# zero_board.net
KiCad netlist of a schematic drawn in EAGLE
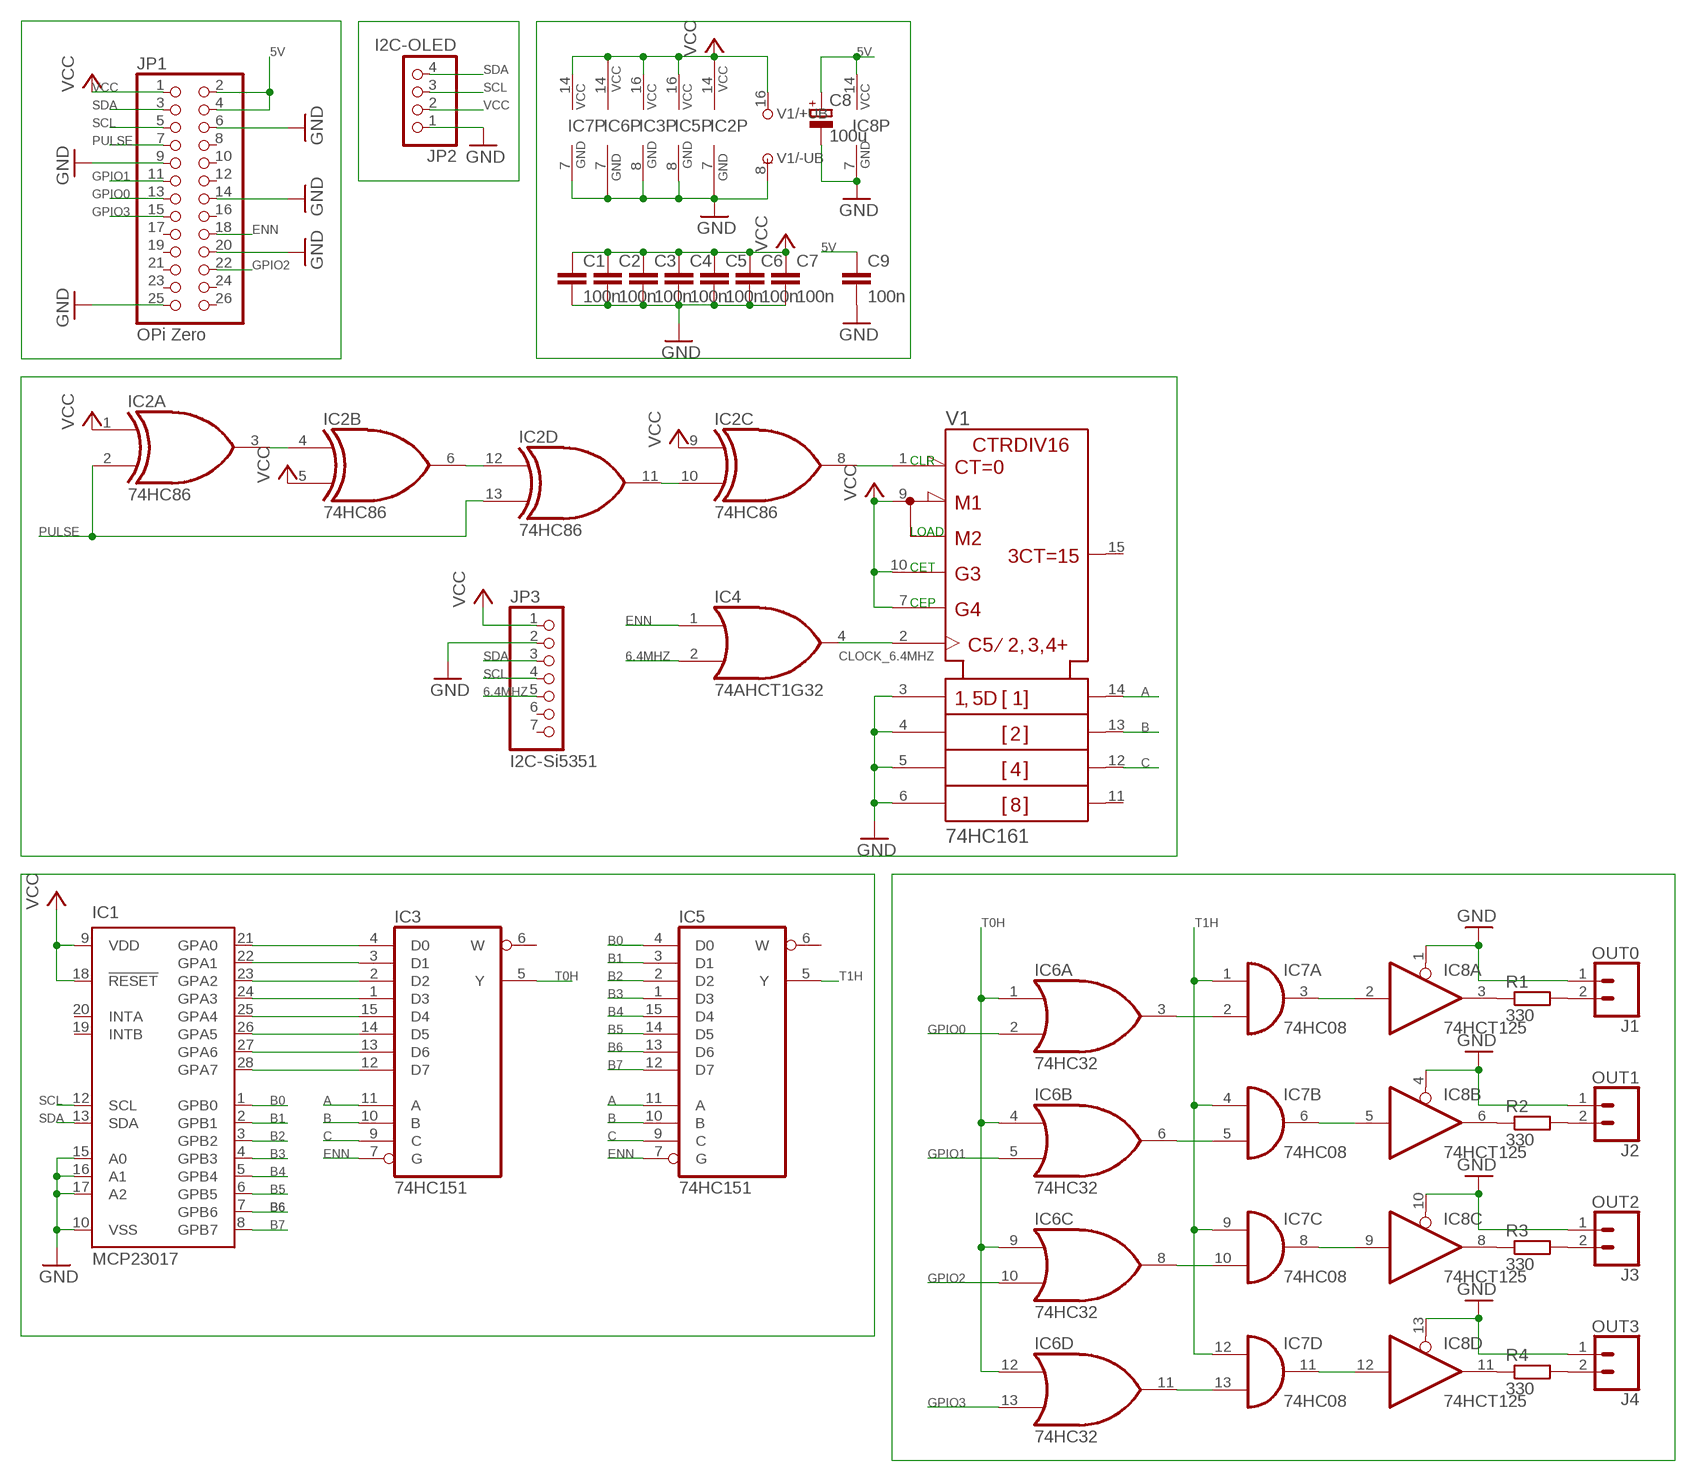
[diagram p0: schematic, sheet 1]

(export (version "E")
  (design (tool "Eeschema 10.0.6"))
  (components
    (comp (ref "C1")
      (value "100n")
      (footprint "eagle-import:C050-024X044")
      (libsource (lib "eagle-import") (part "C-EU050-024X044"))
    )
    (comp (ref "C2")
      (value "100n")
      (footprint "eagle-import:C050-024X044")
      (libsource (lib "eagle-import") (part "C-EU050-024X044"))
    )
    (comp (ref "C3")
      (value "100n")
      (footprint "eagle-import:C050-024X044")
      (libsource (lib "eagle-import") (part "C-EU050-024X044"))
    )
    (comp (ref "C4")
      (value "100n")
      (footprint "eagle-import:C050-024X044")
      (libsource (lib "eagle-import") (part "C-EU050-024X044"))
    )
    (comp (ref "C5")
      (value "100n")
      (footprint "eagle-import:C050-024X044")
      (libsource (lib "eagle-import") (part "C-EU050-024X044"))
    )
    (comp (ref "C6")
      (value "100n")
      (footprint "eagle-import:C050-024X044")
      (libsource (lib "eagle-import") (part "C-EU050-024X044"))
    )
    (comp (ref "C7")
      (value "100n")
      (footprint "eagle-import:C050-024X044")
      (libsource (lib "eagle-import") (part "C-EU050-024X044"))
    )
    (comp (ref "C8")
      (value "100u")
      (footprint "eagle-import:E2,5-6")
      (libsource (lib "eagle-import") (part "CPOL-EUE2.5-6"))
    )
    (comp (ref "C9")
      (value "100n")
      (footprint "eagle-import:C050-024X044")
      (libsource (lib "eagle-import") (part "C-EU050-024X044"))
    )
    (comp (ref "IC1")
      (value "MCP23017")
      (footprint "eagle-import:DIL28-3")
      (fields (field (name "MF") "MICROCHIP") (field (name "MPN") "MCP23017-E/SP"))
      (libsource (lib "eagle-import") (part "MCP23017SP"))
    )
    (comp (ref "IC2")
      (value "74HC86")
      (footprint "eagle-import:DIL14")
      (libsource (lib "eagle-import") (part "7486NLS"))
    )
    (comp (ref "IC3")
      (value "74HC151")
      (footprint "eagle-import:DIL16")
      (libsource (lib "eagle-import") (part "74151NHC"))
    )
    (comp (ref "IC4")
      (value "74AHCT1G32")
      (footprint "eagle-import:SOT23-5")
      (libsource (lib "eagle-import") (part "741G32DBVAHCT"))
    )
    (comp (ref "IC5")
      (value "74HC151")
      (footprint "eagle-import:DIL16")
      (libsource (lib "eagle-import") (part "74151NHC"))
    )
    (comp (ref "IC6")
      (value "74HC32")
      (footprint "eagle-import:DIL14")
      (libsource (lib "eagle-import") (part "7432NLS"))
    )
    (comp (ref "IC7")
      (value "74HC08")
      (footprint "eagle-import:DIL14")
      (libsource (lib "eagle-import") (part "7408NAS"))
    )
    (comp (ref "IC8")
      (value "74HCT125")
      (footprint "eagle-import:DIL14")
      (libsource (lib "eagle-import") (part "74125NHC"))
    )
    (comp (ref "J1")
      (value "OUT0")
      (footprint "eagle-import:SCREWTERMINAL-3.5MM-2")
      (libsource (lib "eagle-import") (part "CONN_023.5MM"))
    )
    (comp (ref "J2")
      (value "OUT1")
      (footprint "eagle-import:SCREWTERMINAL-3.5MM-2")
      (libsource (lib "eagle-import") (part "CONN_023.5MM"))
    )
    (comp (ref "J3")
      (value "OUT2")
      (footprint "eagle-import:SCREWTERMINAL-3.5MM-2")
      (libsource (lib "eagle-import") (part "CONN_023.5MM"))
    )
    (comp (ref "J4")
      (value "OUT3")
      (footprint "eagle-import:SCREWTERMINAL-3.5MM-2")
      (libsource (lib "eagle-import") (part "CONN_023.5MM"))
    )
    (comp (ref "JP1")
      (value "OPi Zero")
      (footprint "eagle-import:2X13")
      (libsource (lib "eagle-import") (part "PINHD-2X13"))
    )
    (comp (ref "JP2")
      (value "I2C-OLED")
      (footprint "eagle-import:1X04")
      (libsource (lib "eagle-import") (part "PINHD-1X4"))
    )
    (comp (ref "JP3")
      (value "I2C-Si5351")
      (footprint "eagle-import:1X07")
      (libsource (lib "eagle-import") (part "PINHD-1X7"))
    )
    (comp (ref "R1")
      (value "330")
      (footprint "eagle-import:0204_5")
      (libsource (lib "eagle-import") (part "R-EU_0204/5"))
    )
    (comp (ref "R2")
      (value "330")
      (footprint "eagle-import:0204_5")
      (libsource (lib "eagle-import") (part "R-EU_0204/5"))
    )
    (comp (ref "R3")
      (value "330")
      (footprint "eagle-import:0204_5")
      (libsource (lib "eagle-import") (part "R-EU_0204/5"))
    )
    (comp (ref "R4")
      (value "330")
      (footprint "eagle-import:0204_5")
      (libsource (lib "eagle-import") (part "R-EU_0204/5"))
    )
    (comp (ref "V1")
      (value "74HC161")
      (footprint "eagle-import:DIL16")
      (libsource (lib "eagle-import") (part "74161N"))
    )
  )
  (nets
    (net (code "1") (name "/5V") (class "Default")
      (node (ref "C8") (pin "+") (pinfunction "+_+") (pintype "passive"))
      (node (ref "C9") (pin "1") (pinfunction "1_1") (pintype "passive"))
      (node (ref "IC8") (pin "14") (pinfunction "VCC_14") (pintype "power_in"))
      (node (ref "JP1") (pin "2") (pinfunction "2_2") (pintype "passive"))
      (node (ref "JP1") (pin "4") (pinfunction "4_4") (pintype "passive"))
    )
    (net (code "2") (name "/6.4MHZ") (class "Default")
      (node (ref "IC4") (pin "2") (pinfunction "I1_2") (pintype "input"))
      (node (ref "JP3") (pin "5") (pinfunction "5_5") (pintype "passive"))
    )
    (net (code "3") (name "/A") (class "Default")
      (node (ref "IC3") (pin "11") (pinfunction "A_11") (pintype "input"))
      (node (ref "IC5") (pin "11") (pinfunction "A_11") (pintype "input"))
      (node (ref "V1") (pin "14") (pinfunction "QA_14") (pintype "output"))
    )
    (net (code "4") (name "/B") (class "Default")
      (node (ref "IC3") (pin "10") (pinfunction "B_10") (pintype "input"))
      (node (ref "IC5") (pin "10") (pinfunction "B_10") (pintype "input"))
      (node (ref "V1") (pin "13") (pinfunction "QB_13") (pintype "output"))
    )
    (net (code "5") (name "/B0") (class "Default")
      (node (ref "IC1") (pin "1") (pinfunction "GPB0_1") (pintype "bidirectional"))
      (node (ref "IC5") (pin "4") (pinfunction "D0_4") (pintype "input"))
    )
    (net (code "6") (name "/B1") (class "Default")
      (node (ref "IC1") (pin "2") (pinfunction "GPB1_2") (pintype "bidirectional"))
      (node (ref "IC5") (pin "3") (pinfunction "D1_3") (pintype "input"))
    )
    (net (code "7") (name "/B2") (class "Default")
      (node (ref "IC1") (pin "3") (pinfunction "GPB2_3") (pintype "bidirectional"))
      (node (ref "IC5") (pin "2") (pinfunction "D2_2") (pintype "input"))
    )
    (net (code "8") (name "/B3") (class "Default")
      (node (ref "IC1") (pin "4") (pinfunction "GPB3_4") (pintype "bidirectional"))
      (node (ref "IC5") (pin "1") (pinfunction "D3_1") (pintype "input"))
    )
    (net (code "9") (name "/B4") (class "Default")
      (node (ref "IC1") (pin "5") (pinfunction "GPB4_5") (pintype "bidirectional"))
      (node (ref "IC5") (pin "15") (pinfunction "D4_15") (pintype "input"))
    )
    (net (code "10") (name "/B5") (class "Default")
      (node (ref "IC1") (pin "6") (pinfunction "GPB5_6") (pintype "bidirectional"))
      (node (ref "IC5") (pin "14") (pinfunction "D5_14") (pintype "input"))
    )
    (net (code "11") (name "/B6") (class "Default")
      (node (ref "IC1") (pin "7") (pinfunction "GPB6_7") (pintype "bidirectional"))
      (node (ref "IC5") (pin "13") (pinfunction "D6_13") (pintype "input"))
    )
    (net (code "12") (name "/B7") (class "Default")
      (node (ref "IC1") (pin "8") (pinfunction "GPB7_8") (pintype "bidirectional"))
      (node (ref "IC5") (pin "12") (pinfunction "D7_12") (pintype "input"))
    )
    (net (code "13") (name "/C") (class "Default")
      (node (ref "IC3") (pin "9") (pinfunction "C_9") (pintype "input"))
      (node (ref "IC5") (pin "9") (pinfunction "C_9") (pintype "input"))
      (node (ref "V1") (pin "12") (pinfunction "QC_12") (pintype "output"))
    )
    (net (code "14") (name "/CLOCK_6.4MHZ") (class "Default")
      (node (ref "IC4") (pin "4") (pinfunction "O_4") (pintype "output"))
      (node (ref "V1") (pin "2") (pinfunction "CLK_2") (pintype "input"))
    )
    (net (code "15") (name "/ENN") (class "Default")
      (node (ref "IC3") (pin "7") (pinfunction "G_7") (pintype "input"))
      (node (ref "IC4") (pin "1") (pinfunction "I0_1") (pintype "input"))
      (node (ref "IC5") (pin "7") (pinfunction "G_7") (pintype "input"))
      (node (ref "JP1") (pin "18") (pinfunction "18_18") (pintype "passive"))
    )
    (net (code "16") (name "/GPIO0") (class "Default")
      (node (ref "IC6") (pin "2") (pinfunction "I1_2") (pintype "input"))
      (node (ref "JP1") (pin "13") (pinfunction "13_13") (pintype "passive"))
    )
    (net (code "17") (name "/GPIO1") (class "Default")
      (node (ref "IC6") (pin "5") (pinfunction "I1_5") (pintype "input"))
      (node (ref "JP1") (pin "11") (pinfunction "11_11") (pintype "passive"))
    )
    (net (code "18") (name "/GPIO2") (class "Default")
      (node (ref "IC6") (pin "10") (pinfunction "I1_10") (pintype "input"))
      (node (ref "JP1") (pin "22") (pinfunction "22_22") (pintype "passive"))
    )
    (net (code "19") (name "/GPIO3") (class "Default")
      (node (ref "IC6") (pin "13") (pinfunction "I1_13") (pintype "input"))
      (node (ref "JP1") (pin "15") (pinfunction "15_15") (pintype "passive"))
    )
    (net (code "20") (name "/PULSE") (class "Default")
      (node (ref "IC2") (pin "13") (pinfunction "I1_13") (pintype "input"))
      (node (ref "IC2") (pin "2") (pinfunction "I1_2") (pintype "input"))
      (node (ref "JP1") (pin "7") (pinfunction "7_7") (pintype "passive"))
    )
    (net (code "21") (name "/SCL") (class "Default")
      (node (ref "IC1") (pin "12") (pinfunction "SCL_12") (pintype "input"))
      (node (ref "JP1") (pin "5") (pinfunction "5_5") (pintype "passive"))
      (node (ref "JP2") (pin "3") (pinfunction "3_3") (pintype "passive"))
      (node (ref "JP3") (pin "4") (pinfunction "4_4") (pintype "passive"))
    )
    (net (code "22") (name "/SDA") (class "Default")
      (node (ref "IC1") (pin "13") (pinfunction "SDA_13") (pintype "bidirectional"))
      (node (ref "JP1") (pin "3") (pinfunction "3_3") (pintype "passive"))
      (node (ref "JP2") (pin "4") (pinfunction "4_4") (pintype "passive"))
      (node (ref "JP3") (pin "3") (pinfunction "3_3") (pintype "passive"))
    )
    (net (code "23") (name "/T0H") (class "Default")
      (node (ref "IC3") (pin "5") (pinfunction "Y_5") (pintype "output"))
      (node (ref "IC6") (pin "1") (pinfunction "I0_1") (pintype "input"))
      (node (ref "IC6") (pin "12") (pinfunction "I0_12") (pintype "input"))
      (node (ref "IC6") (pin "4") (pinfunction "I0_4") (pintype "input"))
      (node (ref "IC6") (pin "9") (pinfunction "I0_9") (pintype "input"))
    )
    (net (code "24") (name "/T1H") (class "Default")
      (node (ref "IC5") (pin "5") (pinfunction "Y_5") (pintype "output"))
      (node (ref "IC7") (pin "1") (pinfunction "I0_1") (pintype "input"))
      (node (ref "IC7") (pin "12") (pinfunction "I0_12") (pintype "input"))
      (node (ref "IC7") (pin "4") (pinfunction "I0_4") (pintype "input"))
      (node (ref "IC7") (pin "9") (pinfunction "I0_9") (pintype "input"))
    )
    (net (code "25") (name "GND") (class "Default")
      (node (ref "C1") (pin "2") (pinfunction "2_2") (pintype "passive"))
      (node (ref "C2") (pin "2") (pinfunction "2_2") (pintype "passive"))
      (node (ref "C3") (pin "2") (pinfunction "2_2") (pintype "passive"))
      (node (ref "C4") (pin "2") (pinfunction "2_2") (pintype "passive"))
      (node (ref "C5") (pin "2") (pinfunction "2_2") (pintype "passive"))
      (node (ref "C6") (pin "2") (pinfunction "2_2") (pintype "passive"))
      (node (ref "C7") (pin "2") (pinfunction "2_2") (pintype "passive"))
      (node (ref "C8") (pin "-") (pinfunction "-_-") (pintype "passive"))
      (node (ref "C9") (pin "2") (pinfunction "2_2") (pintype "passive"))
      (node (ref "IC1") (pin "10") (pinfunction "VSS_10") (pintype "power_in"))
      (node (ref "IC1") (pin "15") (pinfunction "A0_15") (pintype "input"))
      (node (ref "IC1") (pin "16") (pinfunction "A1_16") (pintype "input"))
      (node (ref "IC1") (pin "17") (pinfunction "A2_17") (pintype "input"))
      (node (ref "IC2") (pin "7") (pinfunction "GND_7") (pintype "power_in"))
      (node (ref "IC3") (pin "8") (pinfunction "GND_8") (pintype "power_in"))
      (node (ref "IC5") (pin "8") (pinfunction "GND_8") (pintype "power_in"))
      (node (ref "IC6") (pin "7") (pinfunction "GND_7") (pintype "power_in"))
      (node (ref "IC7") (pin "7") (pinfunction "GND_7") (pintype "power_in"))
      (node (ref "IC8") (pin "1") (pinfunction "OE_1") (pintype "input"))
      (node (ref "IC8") (pin "10") (pinfunction "OE_10") (pintype "input"))
      (node (ref "IC8") (pin "13") (pinfunction "OE_13") (pintype "input"))
      (node (ref "IC8") (pin "4") (pinfunction "OE_4") (pintype "input"))
      (node (ref "IC8") (pin "7") (pinfunction "GND_7") (pintype "power_in"))
      (node (ref "J1") (pin "1") (pinfunction "1_1") (pintype "passive"))
      (node (ref "J2") (pin "1") (pinfunction "1_1") (pintype "passive"))
      (node (ref "J3") (pin "1") (pinfunction "1_1") (pintype "passive"))
      (node (ref "J4") (pin "1") (pinfunction "1_1") (pintype "passive"))
      (node (ref "JP1") (pin "14") (pinfunction "14_14") (pintype "passive"))
      (node (ref "JP1") (pin "20") (pinfunction "20_20") (pintype "passive"))
      (node (ref "JP1") (pin "25") (pinfunction "25_25") (pintype "passive"))
      (node (ref "JP1") (pin "6") (pinfunction "6_6") (pintype "passive"))
      (node (ref "JP1") (pin "9") (pinfunction "9_9") (pintype "passive"))
      (node (ref "JP2") (pin "1") (pinfunction "1_1") (pintype "passive"))
      (node (ref "JP3") (pin "2") (pinfunction "2_2") (pintype "passive"))
      (node (ref "V1") (pin "3") (pinfunction "A_3") (pintype "input"))
      (node (ref "V1") (pin "4") (pinfunction "B_4") (pintype "input"))
      (node (ref "V1") (pin "5") (pinfunction "C_5") (pintype "input"))
      (node (ref "V1") (pin "6") (pinfunction "D_6") (pintype "input"))
      (node (ref "V1") (pin "8") (pinfunction "-UB_8") (pintype "power_in"))
    )
    (net (code "26") (name "Net-(IC1-GPA0)") (class "Default")
      (node (ref "IC1") (pin "21") (pinfunction "GPA0_21") (pintype "bidirectional"))
      (node (ref "IC3") (pin "4") (pinfunction "D0_4") (pintype "input"))
    )
    (net (code "27") (name "Net-(IC1-GPA1)") (class "Default")
      (node (ref "IC1") (pin "22") (pinfunction "GPA1_22") (pintype "bidirectional"))
      (node (ref "IC3") (pin "3") (pinfunction "D1_3") (pintype "input"))
    )
    (net (code "28") (name "Net-(IC1-GPA2)") (class "Default")
      (node (ref "IC1") (pin "23") (pinfunction "GPA2_23") (pintype "bidirectional"))
      (node (ref "IC3") (pin "2") (pinfunction "D2_2") (pintype "input"))
    )
    (net (code "29") (name "Net-(IC1-GPA3)") (class "Default")
      (node (ref "IC1") (pin "24") (pinfunction "GPA3_24") (pintype "bidirectional"))
      (node (ref "IC3") (pin "1") (pinfunction "D3_1") (pintype "input"))
    )
    (net (code "30") (name "Net-(IC1-GPA4)") (class "Default")
      (node (ref "IC1") (pin "25") (pinfunction "GPA4_25") (pintype "bidirectional"))
      (node (ref "IC3") (pin "15") (pinfunction "D4_15") (pintype "input"))
    )
    (net (code "31") (name "Net-(IC1-GPA5)") (class "Default")
      (node (ref "IC1") (pin "26") (pinfunction "GPA5_26") (pintype "bidirectional"))
      (node (ref "IC3") (pin "14") (pinfunction "D5_14") (pintype "input"))
    )
    (net (code "32") (name "Net-(IC1-GPA6)") (class "Default")
      (node (ref "IC1") (pin "27") (pinfunction "GPA6_27") (pintype "bidirectional"))
      (node (ref "IC3") (pin "13") (pinfunction "D6_13") (pintype "input"))
    )
    (net (code "33") (name "Net-(IC1-GPA7)") (class "Default")
      (node (ref "IC1") (pin "28") (pinfunction "GPA7_28") (pintype "bidirectional"))
      (node (ref "IC3") (pin "12") (pinfunction "D7_12") (pintype "input"))
    )
    (net (code "34") (name "Net-(IC2A-O)") (class "Default")
      (node (ref "IC2") (pin "3") (pinfunction "O_3") (pintype "output"))
      (node (ref "IC2") (pin "4") (pinfunction "I0_4") (pintype "input"))
    )
    (net (code "35") (name "Net-(IC2B-O)") (class "Default")
      (node (ref "IC2") (pin "12") (pinfunction "I0_12") (pintype "input"))
      (node (ref "IC2") (pin "6") (pinfunction "O_6") (pintype "output"))
    )
    (net (code "36") (name "Net-(IC2C-I1)") (class "Default")
      (node (ref "IC2") (pin "10") (pinfunction "I1_10") (pintype "input"))
      (node (ref "IC2") (pin "11") (pinfunction "O_11") (pintype "output"))
    )
    (net (code "37") (name "Net-(IC2C-O)") (class "Default")
      (node (ref "IC2") (pin "8") (pinfunction "O_8") (pintype "output"))
      (node (ref "V1") (pin "1") (pinfunction "~{CLR}_1") (pintype "input"))
    )
    (net (code "38") (name "Net-(IC6A-O)") (class "Default")
      (node (ref "IC6") (pin "3") (pinfunction "O_3") (pintype "output"))
      (node (ref "IC7") (pin "2") (pinfunction "I1_2") (pintype "input"))
    )
    (net (code "39") (name "Net-(IC6B-O)") (class "Default")
      (node (ref "IC6") (pin "6") (pinfunction "O_6") (pintype "output"))
      (node (ref "IC7") (pin "5") (pinfunction "I1_5") (pintype "input"))
    )
    (net (code "40") (name "Net-(IC6C-O)") (class "Default")
      (node (ref "IC6") (pin "8") (pinfunction "O_8") (pintype "output"))
      (node (ref "IC7") (pin "10") (pinfunction "I1_10") (pintype "input"))
    )
    (net (code "41") (name "Net-(IC6D-O)") (class "Default")
      (node (ref "IC6") (pin "11") (pinfunction "O_11") (pintype "output"))
      (node (ref "IC7") (pin "13") (pinfunction "I1_13") (pintype "input"))
    )
    (net (code "42") (name "Net-(IC7A-O)") (class "Default")
      (node (ref "IC7") (pin "3") (pinfunction "O_3") (pintype "output"))
      (node (ref "IC8") (pin "2") (pinfunction "I_2") (pintype "input"))
    )
    (net (code "43") (name "Net-(IC7B-O)") (class "Default")
      (node (ref "IC7") (pin "6") (pinfunction "O_6") (pintype "output"))
      (node (ref "IC8") (pin "5") (pinfunction "I_5") (pintype "input"))
    )
    (net (code "44") (name "Net-(IC7C-O)") (class "Default")
      (node (ref "IC7") (pin "8") (pinfunction "O_8") (pintype "output"))
      (node (ref "IC8") (pin "9") (pinfunction "I_9") (pintype "input"))
    )
    (net (code "45") (name "Net-(IC7D-O)") (class "Default")
      (node (ref "IC7") (pin "11") (pinfunction "O_11") (pintype "output"))
      (node (ref "IC8") (pin "12") (pinfunction "I_12") (pintype "input"))
    )
    (net (code "46") (name "Net-(IC8A-O)") (class "Default")
      (node (ref "IC8") (pin "3") (pinfunction "O_3") (pintype "tri_state"))
      (node (ref "R1") (pin "1") (pinfunction "1_1") (pintype "passive"))
    )
    (net (code "47") (name "Net-(IC8B-O)") (class "Default")
      (node (ref "IC8") (pin "6") (pinfunction "O_6") (pintype "tri_state"))
      (node (ref "R2") (pin "1") (pinfunction "1_1") (pintype "passive"))
    )
    (net (code "48") (name "Net-(IC8C-O)") (class "Default")
      (node (ref "IC8") (pin "8") (pinfunction "O_8") (pintype "tri_state"))
      (node (ref "R3") (pin "1") (pinfunction "1_1") (pintype "passive"))
    )
    (net (code "49") (name "Net-(IC8D-O)") (class "Default")
      (node (ref "IC8") (pin "11") (pinfunction "O_11") (pintype "tri_state"))
      (node (ref "R4") (pin "1") (pinfunction "1_1") (pintype "passive"))
    )
    (net (code "50") (name "Net-(J1-Pad2)") (class "Default")
      (node (ref "J1") (pin "2") (pinfunction "2_2") (pintype "passive"))
      (node (ref "R1") (pin "2") (pinfunction "2_2") (pintype "passive"))
    )
    (net (code "51") (name "Net-(J2-Pad2)") (class "Default")
      (node (ref "J2") (pin "2") (pinfunction "2_2") (pintype "passive"))
      (node (ref "R2") (pin "2") (pinfunction "2_2") (pintype "passive"))
    )
    (net (code "52") (name "Net-(J3-Pad2)") (class "Default")
      (node (ref "J3") (pin "2") (pinfunction "2_2") (pintype "passive"))
      (node (ref "R3") (pin "2") (pinfunction "2_2") (pintype "passive"))
    )
    (net (code "53") (name "Net-(J4-Pad2)") (class "Default")
      (node (ref "J4") (pin "2") (pinfunction "2_2") (pintype "passive"))
      (node (ref "R4") (pin "2") (pinfunction "2_2") (pintype "passive"))
    )
    (net (code "54") (name "VCC") (class "Default")
      (node (ref "C1") (pin "1") (pinfunction "1_1") (pintype "passive"))
      (node (ref "C2") (pin "1") (pinfunction "1_1") (pintype "passive"))
      (node (ref "C3") (pin "1") (pinfunction "1_1") (pintype "passive"))
      (node (ref "C4") (pin "1") (pinfunction "1_1") (pintype "passive"))
      (node (ref "C5") (pin "1") (pinfunction "1_1") (pintype "passive"))
      (node (ref "C6") (pin "1") (pinfunction "1_1") (pintype "passive"))
      (node (ref "C7") (pin "1") (pinfunction "1_1") (pintype "passive"))
      (node (ref "IC1") (pin "18") (pinfunction "~{RESET}_18") (pintype "input"))
      (node (ref "IC1") (pin "9") (pinfunction "VDD_9") (pintype "power_in"))
      (node (ref "IC2") (pin "1") (pinfunction "I0_1") (pintype "input"))
      (node (ref "IC2") (pin "14") (pinfunction "VCC_14") (pintype "power_in"))
      (node (ref "IC2") (pin "5") (pinfunction "I1_5") (pintype "input"))
      (node (ref "IC2") (pin "9") (pinfunction "I0_9") (pintype "input"))
      (node (ref "IC3") (pin "16") (pinfunction "VCC_16") (pintype "power_in"))
      (node (ref "IC5") (pin "16") (pinfunction "VCC_16") (pintype "power_in"))
      (node (ref "IC6") (pin "14") (pinfunction "VCC_14") (pintype "power_in"))
      (node (ref "IC7") (pin "14") (pinfunction "VCC_14") (pintype "power_in"))
      (node (ref "JP1") (pin "1") (pinfunction "1_1") (pintype "passive"))
      (node (ref "JP2") (pin "2") (pinfunction "2_2") (pintype "passive"))
      (node (ref "JP3") (pin "1") (pinfunction "1_1") (pintype "passive"))
      (node (ref "V1") (pin "10") (pinfunction "ENT_10") (pintype "input"))
      (node (ref "V1") (pin "16") (pinfunction "+UB_16") (pintype "power_in"))
      (node (ref "V1") (pin "7") (pinfunction "ENP_7") (pintype "input"))
      (node (ref "V1") (pin "9") (pinfunction "~{LOAD}_9") (pintype "input"))
    )
    (net (code "55") (name "unconnected-(IC1-INTA-Pad20)") (class "Default")
      (node (ref "IC1") (pin "20") (pinfunction "INTA_20") (pintype "output"))
    )
    (net (code "56") (name "unconnected-(IC1-INTB-Pad19)") (class "Default")
      (node (ref "IC1") (pin "19") (pinfunction "INTB_19") (pintype "output"))
    )
    (net (code "57") (name "unconnected-(IC3A-W-Pad6)") (class "Default")
      (node (ref "IC3") (pin "6") (pinfunction "W_6") (pintype "output"))
    )
    (net (code "58") (name "unconnected-(IC5A-W-Pad6)") (class "Default")
      (node (ref "IC5") (pin "6") (pinfunction "W_6") (pintype "output"))
    )
    (net (code "59") (name "unconnected-(JP1-Pad8)") (class "Default")
      (node (ref "JP1") (pin "8") (pinfunction "8_8") (pintype "passive"))
    )
    (net (code "60") (name "unconnected-(JP1-Pad10)") (class "Default")
      (node (ref "JP1") (pin "10") (pinfunction "10_10") (pintype "passive"))
    )
    (net (code "61") (name "unconnected-(JP1-Pad12)") (class "Default")
      (node (ref "JP1") (pin "12") (pinfunction "12_12") (pintype "passive"))
    )
    (net (code "62") (name "unconnected-(JP1-Pad16)") (class "Default")
      (node (ref "JP1") (pin "16") (pinfunction "16_16") (pintype "passive"))
    )
    (net (code "63") (name "unconnected-(JP1-Pad17)") (class "Default")
      (node (ref "JP1") (pin "17") (pinfunction "17_17") (pintype "passive"))
    )
    (net (code "64") (name "unconnected-(JP1-Pad19)") (class "Default")
      (node (ref "JP1") (pin "19") (pinfunction "19_19") (pintype "passive"))
    )
    (net (code "65") (name "unconnected-(JP1-Pad21)") (class "Default")
      (node (ref "JP1") (pin "21") (pinfunction "21_21") (pintype "passive"))
    )
    (net (code "66") (name "unconnected-(JP1-Pad23)") (class "Default")
      (node (ref "JP1") (pin "23") (pinfunction "23_23") (pintype "passive"))
    )
    (net (code "67") (name "unconnected-(JP1-Pad24)") (class "Default")
      (node (ref "JP1") (pin "24") (pinfunction "24_24") (pintype "passive"))
    )
    (net (code "68") (name "unconnected-(JP1-Pad26)") (class "Default")
      (node (ref "JP1") (pin "26") (pinfunction "26_26") (pintype "passive"))
    )
    (net (code "69") (name "unconnected-(JP3-Pad6)") (class "Default")
      (node (ref "JP3") (pin "6") (pinfunction "6_6") (pintype "passive"))
    )
    (net (code "70") (name "unconnected-(JP3-Pad7)") (class "Default")
      (node (ref "JP3") (pin "7") (pinfunction "7_7") (pintype "passive"))
    )
    (net (code "71") (name "unconnected-(V1C-QD-Pad11)") (class "Default")
      (node (ref "V1") (pin "11") (pinfunction "QD_11") (pintype "output"))
    )
    (net (code "72") (name "unconnected-(V1C-RCO-Pad15)") (class "Default")
      (node (ref "V1") (pin "15") (pinfunction "RCO_15") (pintype "output"))
    )
  )
)
